# Connectors.net
KiCad netlist of a schematic drawn in Altium Designer
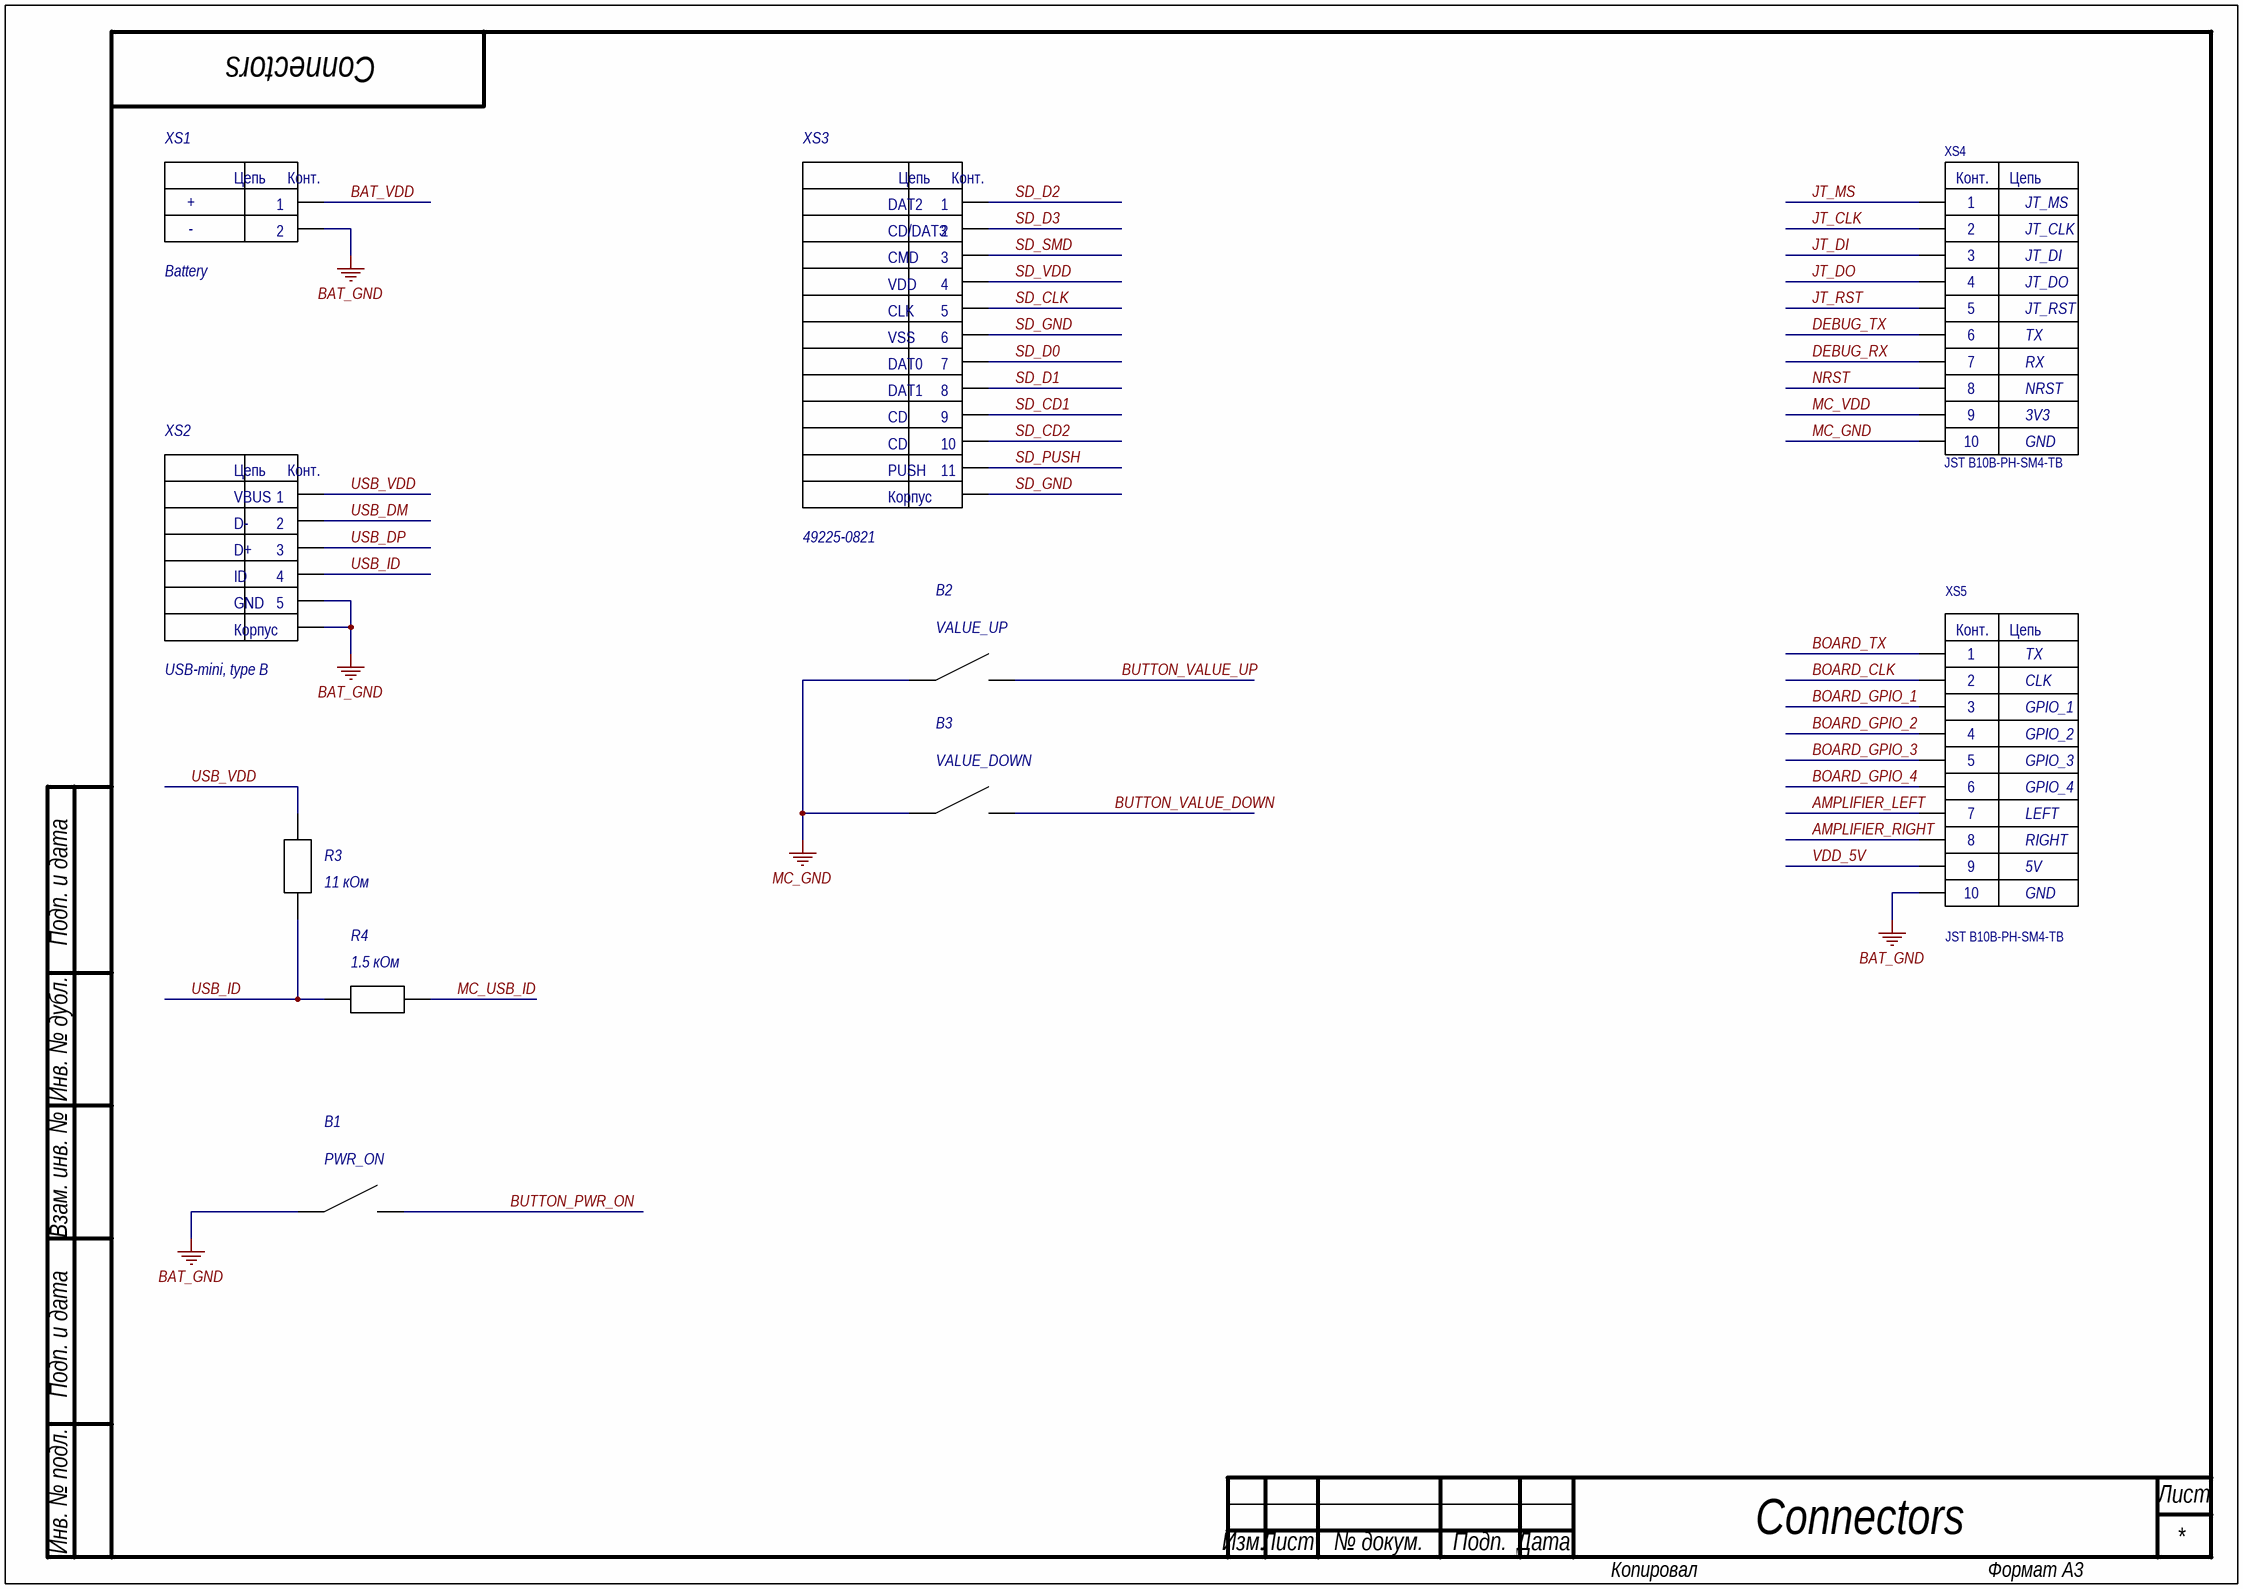
[diagram p0: Connectors.SchDoc]

(export (version "E")
  (design (tool "Eeschema 10.0.6"))
  (components
    (comp (ref "B1")
      (value "BUTTON")
      (footprint "TACT SKHH Horizontal Switch")
      (libsource (lib "my_lib") (part "BUTTON"))
    )
    (comp (ref "B2")
      (value "BUTTON")
      (footprint "TACT SKHH Horizontal Switch")
      (libsource (lib "my_lib") (part "BUTTON"))
    )
    (comp (ref "B3")
      (value "BUTTON")
      (footprint "TACT SKHH Horizontal Switch")
      (libsource (lib "my_lib") (part "BUTTON"))
    )
    (comp (ref "R3") (value "11 кОм") (footprint "RES 0402") (libsource (lib "my_lib") (part "RES 0402")))
    (comp (ref "R4") (value "1.5 кОм") (footprint "RES 0402") (libsource (lib "my_lib") (part "RES 0402")))
    (comp (ref "XS1")
      (value "Battery")
      (footprint "JST B2B-PH-SM4-TB")
      (libsource (lib "my_lib") (part "JST B2B-PH-SM4-TB"))
    )
    (comp (ref "XS2")
      (value "USB-mini, type B")
      (footprint "USB_mini_B")
      (description "USB-mini-B connector")
      (fields (field (name "MANUFACTURER") "NONAME"))
      (libsource (lib "my_lib") (part "USB-mini_B"))
    )
    (comp (ref "XS3")
      (value "49225-0821")
      (footprint "MOLEX 49225-0821")
      (description "MOLEX MicroSD connector")
      (fields (field (name "MANUFACTURER") "Molex"))
      (libsource (lib "my_lib") (part "49225-0821"))
    )
    (comp (ref "XS4")
      (value "JST B10B-PH-SM4-TB")
      (footprint "B10B-PH-SM4-TB")
      (description "PLS connector")
      (fields (field (name "MANUFACTURER") "NONAME"))
      (libsource (lib "my_lib") (part "JST B10B-PH-SM4-TB"))
    )
    (comp (ref "XS5")
      (value "JST B10B-PH-SM4-TB")
      (footprint "B10B-PH-SM4-TB")
      (description "PLS connector")
      (fields (field (name "MANUFACTURER") "NONAME"))
      (libsource (lib "my_lib") (part "JST B10B-PH-SM4-TB"))
    )
  )
  (nets
    (net (code "1") (name "/AMPLIFIER_LEFT") (class "Default")
      (node (ref "XS5") (pin "7") (pinfunction "7_7") (pintype "passive"))
    )
    (net (code "2") (name "/AMPLIFIER_RIGHT") (class "Default")
      (node (ref "XS5") (pin "8") (pinfunction "8_8") (pintype "passive"))
    )
    (net (code "3") (name "/BAT_VDD") (class "Default")
      (node (ref "XS1") (pin "1") (pinfunction "1_1") (pintype "passive"))
    )
    (net (code "4") (name "/BOARD_CLK") (class "Default")
      (node (ref "XS5") (pin "2") (pinfunction "2_2") (pintype "passive"))
    )
    (net (code "5") (name "/BOARD_GPIO_1") (class "Default")
      (node (ref "XS5") (pin "3") (pinfunction "3_3") (pintype "passive"))
    )
    (net (code "6") (name "/BOARD_GPIO_2") (class "Default")
      (node (ref "XS5") (pin "4") (pinfunction "4_4") (pintype "passive"))
    )
    (net (code "7") (name "/BOARD_GPIO_3") (class "Default")
      (node (ref "XS5") (pin "5") (pinfunction "5_5") (pintype "passive"))
    )
    (net (code "8") (name "/BOARD_GPIO_4") (class "Default")
      (node (ref "XS5") (pin "6") (pinfunction "6_6") (pintype "passive"))
    )
    (net (code "9") (name "/BOARD_TX") (class "Default")
      (node (ref "XS5") (pin "1") (pinfunction "1_1") (pintype "passive"))
    )
    (net (code "10") (name "/BUTTON_PWR_ON") (class "Default")
      (node (ref "B1") (pin "2") (pinfunction "2_2") (pintype "passive"))
    )
    (net (code "11") (name "/BUTTON_VALUE_DOWN") (class "Default")
      (node (ref "B3") (pin "2") (pinfunction "2_2") (pintype "passive"))
    )
    (net (code "12") (name "/BUTTON_VALUE_UP") (class "Default")
      (node (ref "B2") (pin "2") (pinfunction "2_2") (pintype "passive"))
    )
    (net (code "13") (name "/DEBUG_RX") (class "Default")
      (node (ref "XS4") (pin "7") (pinfunction "7_7") (pintype "passive"))
    )
    (net (code "14") (name "/DEBUG_TX") (class "Default")
      (node (ref "XS4") (pin "6") (pinfunction "6_6") (pintype "passive"))
    )
    (net (code "15") (name "/JT_CLK") (class "Default")
      (node (ref "XS4") (pin "2") (pinfunction "2_2") (pintype "passive"))
    )
    (net (code "16") (name "/JT_DI") (class "Default")
      (node (ref "XS4") (pin "3") (pinfunction "3_3") (pintype "passive"))
    )
    (net (code "17") (name "/JT_DO") (class "Default")
      (node (ref "XS4") (pin "4") (pinfunction "4_4") (pintype "passive"))
    )
    (net (code "18") (name "/JT_MS") (class "Default")
      (node (ref "XS4") (pin "1") (pinfunction "1_1") (pintype "passive"))
    )
    (net (code "19") (name "/JT_RST") (class "Default")
      (node (ref "XS4") (pin "5") (pinfunction "5_5") (pintype "passive"))
    )
    (net (code "20") (name "/MC_USB_ID") (class "Default")
      (node (ref "R4") (pin "1") (pinfunction "1_1") (pintype "passive"))
    )
    (net (code "21") (name "/MC_VDD") (class "Default")
      (node (ref "XS4") (pin "9") (pinfunction "9_9") (pintype "passive"))
    )
    (net (code "22") (name "/NRST") (class "Default")
      (node (ref "XS4") (pin "8") (pinfunction "8_8") (pintype "passive"))
    )
    (net (code "23") (name "/SD_CD1") (class "Default")
      (node (ref "XS3") (pin "9") (pinfunction "9_9") (pintype "passive"))
    )
    (net (code "24") (name "/SD_CD2") (class "Default")
      (node (ref "XS3") (pin "10") (pinfunction "10_10") (pintype "passive"))
    )
    (net (code "25") (name "/SD_CLK") (class "Default")
      (node (ref "XS3") (pin "5") (pinfunction "5_5") (pintype "passive"))
    )
    (net (code "26") (name "/SD_D0") (class "Default")
      (node (ref "XS3") (pin "7") (pinfunction "7_7") (pintype "passive"))
    )
    (net (code "27") (name "/SD_D1") (class "Default")
      (node (ref "XS3") (pin "8") (pinfunction "8_8") (pintype "passive"))
    )
    (net (code "28") (name "/SD_D2") (class "Default")
      (node (ref "XS3") (pin "1") (pinfunction "1_1") (pintype "passive"))
    )
    (net (code "29") (name "/SD_D3") (class "Default")
      (node (ref "XS3") (pin "2") (pinfunction "2_2") (pintype "passive"))
    )
    (net (code "30") (name "/SD_GND") (class "Default")
      (node (ref "XS3") (pin "0") (pinfunction "0_0") (pintype "passive"))
      (node (ref "XS3") (pin "6") (pinfunction "6_6") (pintype "passive"))
    )
    (net (code "31") (name "/SD_PUSH") (class "Default")
      (node (ref "XS3") (pin "11") (pinfunction "11_11") (pintype "passive"))
    )
    (net (code "32") (name "/SD_SMD") (class "Default")
      (node (ref "XS3") (pin "3") (pinfunction "3_3") (pintype "passive"))
    )
    (net (code "33") (name "/SD_VDD") (class "Default")
      (node (ref "XS3") (pin "4") (pinfunction "4_4") (pintype "passive"))
    )
    (net (code "34") (name "/USB_DM") (class "Default")
      (node (ref "XS2") (pin "2") (pinfunction "D-_2") (pintype "passive"))
    )
    (net (code "35") (name "/USB_DP") (class "Default")
      (node (ref "XS2") (pin "3") (pinfunction "D+_3") (pintype "passive"))
    )
    (net (code "36") (name "/USB_ID") (class "Default")
      (node (ref "R3") (pin "1") (pinfunction "1_1") (pintype "passive"))
      (node (ref "R4") (pin "2") (pinfunction "2_2") (pintype "passive"))
      (node (ref "XS2") (pin "4") (pinfunction "CASE_4") (pintype "passive"))
    )
    (net (code "37") (name "/USB_VDD") (class "Default")
      (node (ref "R3") (pin "2") (pinfunction "2_2") (pintype "passive"))
      (node (ref "XS2") (pin "1") (pinfunction "VBUS_1") (pintype "passive"))
    )
    (net (code "38") (name "/VDD_5V") (class "Default")
      (node (ref "XS5") (pin "9") (pinfunction "9_9") (pintype "passive"))
    )
    (net (code "39") (name "BAT_GND") (class "Default")
      (node (ref "B1") (pin "1") (pinfunction "1_1") (pintype "passive"))
      (node (ref "XS1") (pin "2") (pinfunction "2_2") (pintype "passive"))
      (node (ref "XS2") (pin "0") (pinfunction "0_0") (pintype "passive"))
      (node (ref "XS2") (pin "5") (pinfunction "GND_5") (pintype "passive"))
      (node (ref "XS5") (pin "10") (pinfunction "10_10") (pintype "passive"))
    )
    (net (code "40") (name "MC_GND") (class "Default")
      (node (ref "B2") (pin "1") (pinfunction "1_1") (pintype "passive"))
      (node (ref "B3") (pin "1") (pinfunction "1_1") (pintype "passive"))
      (node (ref "XS4") (pin "10") (pinfunction "10_10") (pintype "passive"))
    )
  )
)
